# degen.net
KiCad netlist of a schematic drawn in EAGLE
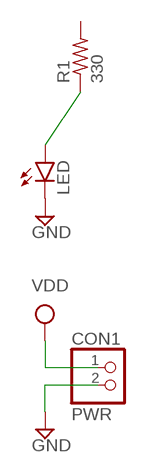
[diagram p0: schematic, sheet 1]

(export (version "E")
  (design (tool "Eeschema 10.0.6"))
  (components
    (comp (ref "CON1")
      (value "PWR")
      (footprint "eagle-import:1X02")
      (libsource (lib "eagle-import") (part "PINHD-1X2"))
    )
    (comp (ref "LED")
      (value "LED3MM")
      (footprint "eagle-import:LED3MM")
      (libsource (lib "eagle-import") (part "LED3MM"))
    )
    (comp (ref "R1")
      (value "330")
      (footprint "eagle-import:0204_7")
      (libsource (lib "eagle-import") (part "R-US_0204/7"))
    )
  )
  (nets
    (net (code "1") (name "GND") (class "Default")
      (node (ref "CON1") (pin "2") (pinfunction "2_2") (pintype "passive"))
      (node (ref "LED") (pin "K") (pinfunction "C_K") (pintype "passive"))
    )
    (net (code "2") (name "Net-(LED-PadA)") (class "Default")
      (node (ref "LED") (pin "A") (pinfunction "A_A") (pintype "passive"))
      (node (ref "R1") (pin "1") (pinfunction "1_1") (pintype "passive"))
    )
    (net (code "3") (name "VDD") (class "Default")
      (node (ref "CON1") (pin "1") (pinfunction "1_1") (pintype "passive"))
    )
    (net (code "4") (name "unconnected-(R1-Pad2)") (class "Default")
      (node (ref "R1") (pin "2") (pinfunction "2_2") (pintype "passive"))
    )
  )
)
